# USB2Serial.net
KiCad netlist of a schematic drawn in Altium Designer
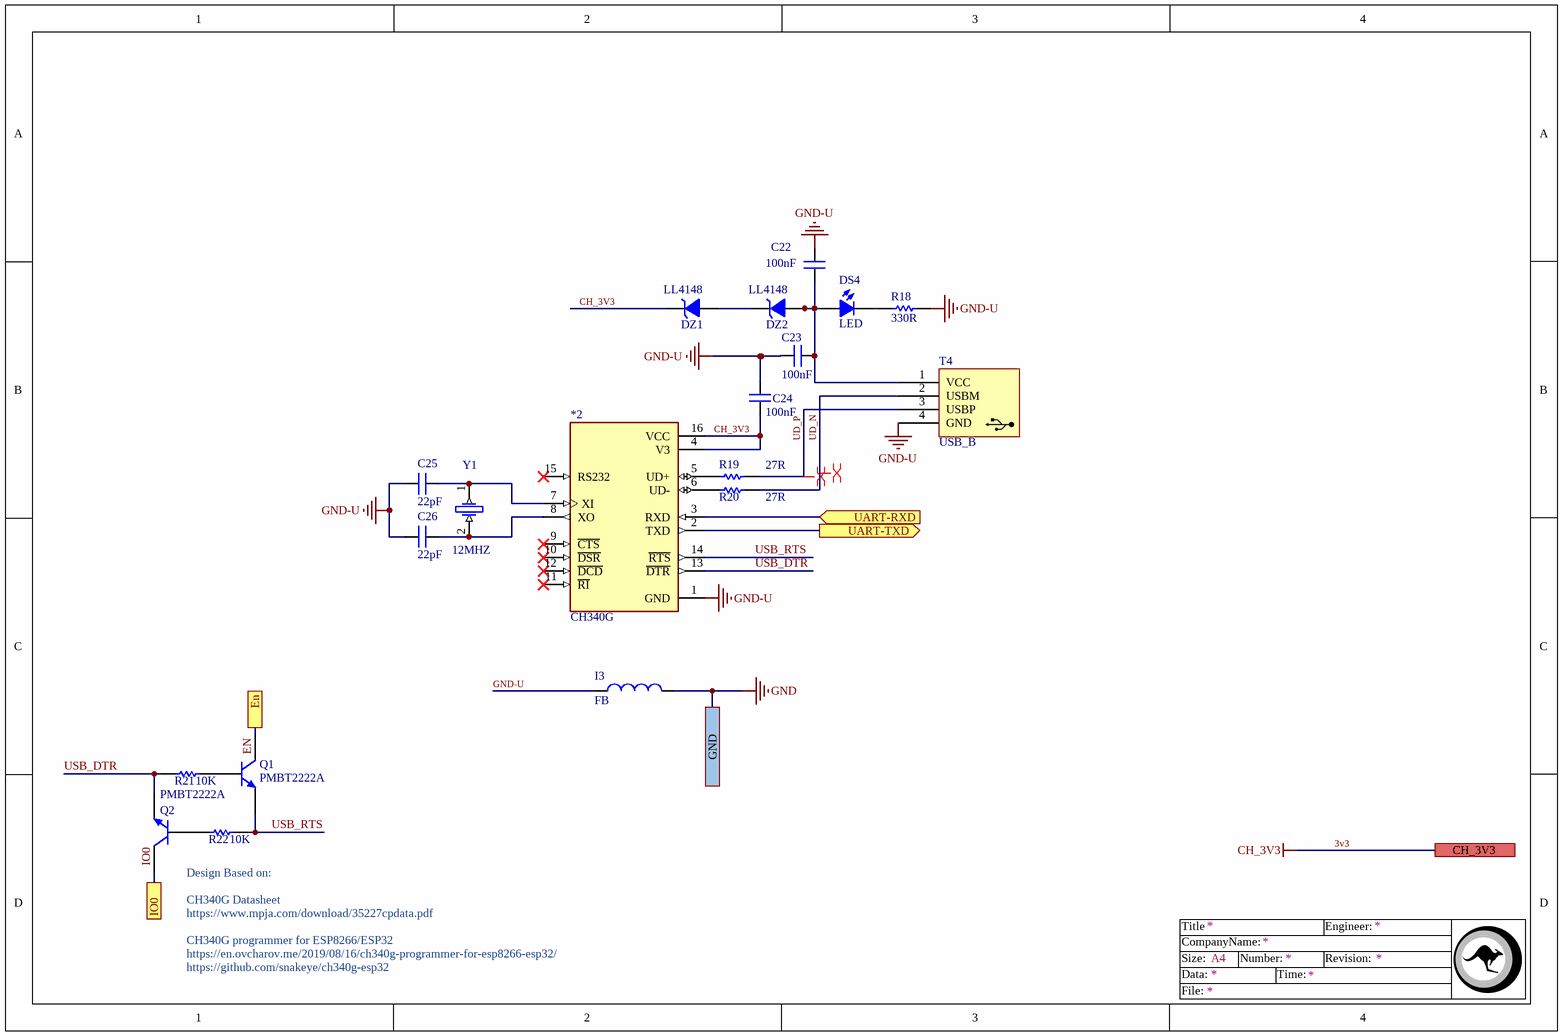
[diagram p0: USB2Serial.SchDoc]

(export (version "E")
  (design (tool "Eeschema 10.0.6"))
  (components
    (comp (ref "*2")
      (value "CH340G")
      (footprint "SOIC127P600X180-16N")
      (libsource (lib "PMLIB2020-V3") (part "CH340G"))
    )
    (comp (ref "C22")
      (value "100nF")
      (footprint "Cap0805")
      (description "Surface mount Capacitor")
      (libsource (lib "PMLIB2020-V3") (part "Cap"))
    )
    (comp (ref "C23")
      (value "100nF")
      (footprint "Cap0805")
      (description "Surface mount Capacitor")
      (libsource (lib "PMLIB2020-V3") (part "Cap"))
    )
    (comp (ref "C24")
      (value "100nF")
      (footprint "Cap0805")
      (description "Surface mount Capacitor")
      (libsource (lib "PMLIB2020-V3") (part "Cap"))
    )
    (comp (ref "C25")
      (value "22pF")
      (footprint "Cap0805")
      (description "Surface mount Capacitor")
      (libsource (lib "PMLIB2020-V3") (part "Cap"))
    )
    (comp (ref "C26")
      (value "22pF")
      (footprint "Cap0805")
      (description "Surface mount Capacitor")
      (libsource (lib "PMLIB2020-V3") (part "Cap"))
    )
    (comp (ref "DS4") (value "LED") (footprint "LED_0805Green") (libsource (lib "PMLIB2020-V3") (part "LED")))
    (comp (ref "DZ1")
      (value "LL4148")
      (footprint "LL4148")
      (description "Diode Zener")
      (libsource (lib "PMLIB2020-V3") (part "Diode Zener"))
    )
    (comp (ref "DZ2")
      (value "LL4148")
      (footprint "LL4148")
      (description "Diode Zener")
      (libsource (lib "PMLIB2020-V3") (part "Diode Zener"))
    )
    (comp (ref "I3")
      (value "FB")
      (footprint "1206")
      (description "Indicator")
      (libsource (lib "PMLIB2020-V3") (part "Inductor"))
    )
    (comp (ref "Q1")
      (value "PMBT2222A")
      (footprint "SOT23_BEC_N")
      (description "NPN Bipolar Transistor")
      (fields (field (name "PUBLISHER") "Altium Limited"))
      (libsource (lib "PMLIB2020-V3") (part "NPN"))
    )
    (comp (ref "Q2")
      (value "PMBT2222A")
      (footprint "SOT23_BEC_N")
      (description "NPN Bipolar Transistor")
      (fields (field (name "PUBLISHER") "Altium Limited"))
      (libsource (lib "PMLIB2020-V3") (part "NPN"))
    )
    (comp (ref "R18")
      (value "330R")
      (footprint "R0805")
      (description "Resistor")
      (libsource (lib "PMLIB2020-V3") (part "Resistor"))
    )
    (comp (ref "R19")
      (value "27R")
      (footprint "R0805")
      (description "Resistor")
      (libsource (lib "PMLIB2020-V3") (part "Resistor"))
    )
    (comp (ref "R20")
      (value "27R")
      (footprint "R0805")
      (description "Resistor")
      (libsource (lib "PMLIB2020-V3") (part "Resistor"))
    )
    (comp (ref "R21")
      (value "10K")
      (footprint "R0805")
      (description "Resistor")
      (libsource (lib "PMLIB2020-V3") (part "Resistor"))
    )
    (comp (ref "R22")
      (value "10K")
      (footprint "R0805")
      (description "Resistor")
      (libsource (lib "PMLIB2020-V3") (part "Resistor"))
    )
    (comp (ref "T4")
      (value "USB_B")
      (footprint "USB_Dip_R")
      (description "USB B Connector")
      (libsource (lib "PMLIB2020-V3") (part "USB_B"))
    )
    (comp (ref "Y1")
      (value "12MHZ")
      (footprint "Crystal SMD")
      (description "Crystal")
      (libsource (lib "PMLIB2020-V3") (part "Crystal"))
    )
  )
  (nets
    (net (code "2") (name "/En") (class "Default")
      (node (ref "Q1") (pin "3") (pinfunction "C_3") (pintype "passive"))
    )
    (net (code "3") (name "/IO0") (class "Default")
      (node (ref "Q2") (pin "3") (pinfunction "C_3") (pintype "passive"))
    )
    (net (code "4") (name "/UART-RXD") (class "Default")
      (node (ref "*2") (pin "3") (pinfunction "RXD_3") (pintype "input"))
    )
    (net (code "5") (name "/UART-TXD") (class "Default")
      (node (ref "*2") (pin "2") (pinfunction "TXD_2") (pintype "output"))
    )
    (net (code "6") (name "/UD_N") (class "Default")
      (node (ref "R20") (pin "1") (pinfunction "1_1") (pintype "passive"))
      (node (ref "T4") (pin "2") (pinfunction "USBM_2") (pintype "passive"))
    )
    (net (code "7") (name "/UD_P") (class "Default")
      (node (ref "R19") (pin "1") (pinfunction "1_1") (pintype "passive"))
      (node (ref "T4") (pin "3") (pinfunction "USBP_3") (pintype "passive"))
    )
    (net (code "8") (name "/USB_DTR") (class "Default")
      (node (ref "*2") (pin "13") (pinfunction "~{DTR}_13") (pintype "output"))
      (node (ref "Q2") (pin "2") (pinfunction "E_2") (pintype "passive"))
      (node (ref "R21") (pin "2") (pinfunction "2_2") (pintype "passive"))
    )
    (net (code "9") (name "/USB_RTS") (class "Default")
      (node (ref "*2") (pin "14") (pinfunction "~{RTS}_14") (pintype "output"))
      (node (ref "Q1") (pin "2") (pinfunction "E_2") (pintype "passive"))
      (node (ref "R22") (pin "1") (pinfunction "1_1") (pintype "passive"))
    )
    (net (code "10") (name "CH_3V3") (class "Default")
      (node (ref "*2") (pin "16") (pinfunction "VCC_16") (pintype "power_in"))
      (node (ref "*2") (pin "4") (pinfunction "V3_4") (pintype "power_in"))
      (node (ref "C24") (pin "2") (pinfunction "2_2") (pintype "passive"))
      (node (ref "DZ1") (pin "K") (pinfunction "K_K") (pintype "passive"))
    )
    (net (code "11") (name "GND") (class "Default")
      (node (ref "I3") (pin "2") (pinfunction "2_2") (pintype "passive"))
    )
    (net (code "12") (name "GND-U") (class "Default")
      (node (ref "*2") (pin "1") (pinfunction "GND_1") (pintype "power_in"))
      (node (ref "C22") (pin "2") (pinfunction "2_2") (pintype "passive"))
      (node (ref "C23") (pin "2") (pinfunction "2_2") (pintype "passive"))
      (node (ref "C24") (pin "1") (pinfunction "1_1") (pintype "passive"))
      (node (ref "C25") (pin "2") (pinfunction "2_2") (pintype "passive"))
      (node (ref "C26") (pin "2") (pinfunction "2_2") (pintype "passive"))
      (node (ref "I3") (pin "1") (pinfunction "1_1") (pintype "passive"))
      (node (ref "R18") (pin "1") (pinfunction "1_1") (pintype "passive"))
      (node (ref "T4") (pin "4") (pinfunction "GND_4") (pintype "passive"))
    )
    (net (code "13") (name "Net-(*2-UD+)") (class "Default")
      (node (ref "*2") (pin "5") (pinfunction "UD+_5") (pintype "bidirectional"))
      (node (ref "R19") (pin "2") (pinfunction "2_2") (pintype "passive"))
    )
    (net (code "14") (name "Net-(*2-UD-)") (class "Default")
      (node (ref "*2") (pin "6") (pinfunction "UD-_6") (pintype "bidirectional"))
      (node (ref "R20") (pin "2") (pinfunction "2_2") (pintype "passive"))
    )
    (net (code "15") (name "Net-(*2-XI)") (class "Default")
      (node (ref "*2") (pin "7") (pinfunction "XI_7") (pintype "input"))
      (node (ref "C25") (pin "1") (pinfunction "1_1") (pintype "passive"))
      (node (ref "Y1") (pin "1") (pinfunction "1_1") (pintype "output"))
    )
    (net (code "16") (name "Net-(*2-XO)") (class "Default")
      (node (ref "*2") (pin "8") (pinfunction "XO_8") (pintype "output"))
      (node (ref "C26") (pin "1") (pinfunction "1_1") (pintype "passive"))
      (node (ref "Y1") (pin "2") (pinfunction "2_2") (pintype "input"))
    )
    (net (code "17") (name "Net-(DS4-PadK)") (class "Default")
      (node (ref "DS4") (pin "K") (pinfunction "K_K") (pintype "passive"))
      (node (ref "R18") (pin "2") (pinfunction "2_2") (pintype "passive"))
    )
    (net (code "18") (name "Net-(DZ1-PadA)") (class "Default")
      (node (ref "DZ1") (pin "A") (pinfunction "A_A") (pintype "passive"))
      (node (ref "DZ2") (pin "K") (pinfunction "K_K") (pintype "passive"))
    )
    (net (code "19") (name "Net-(Q1-B)") (class "Default")
      (node (ref "Q1") (pin "1") (pinfunction "B_1") (pintype "passive"))
      (node (ref "R21") (pin "1") (pinfunction "1_1") (pintype "passive"))
    )
    (net (code "20") (name "Net-(Q2-B)") (class "Default")
      (node (ref "Q2") (pin "1") (pinfunction "B_1") (pintype "passive"))
      (node (ref "R22") (pin "2") (pinfunction "2_2") (pintype "passive"))
    )
    (net (code "21") (name "Net-(T4-VCC)") (class "Default")
      (node (ref "C22") (pin "1") (pinfunction "1_1") (pintype "passive"))
      (node (ref "C23") (pin "1") (pinfunction "1_1") (pintype "passive"))
      (node (ref "DS4") (pin "A") (pinfunction "A_A") (pintype "passive"))
      (node (ref "DZ2") (pin "A") (pinfunction "A_A") (pintype "passive"))
      (node (ref "T4") (pin "1") (pinfunction "VCC_1") (pintype "passive"))
    )
    (net (code "22") (name "unconnected-(*2-RS232-Pad15)") (class "Default")
      (node (ref "*2") (pin "15") (pinfunction "RS232_15") (pintype "input+no_connect"))
    )
    (net (code "23") (name "unconnected-(*2-~{CTS}-Pad9)") (class "Default")
      (node (ref "*2") (pin "9") (pinfunction "~{CTS}_9") (pintype "input+no_connect"))
    )
    (net (code "24") (name "unconnected-(*2-~{DCD}-Pad12)") (class "Default")
      (node (ref "*2") (pin "12") (pinfunction "~{DCD}_12") (pintype "input+no_connect"))
    )
    (net (code "25") (name "unconnected-(*2-~{DSR}-Pad10)") (class "Default")
      (node (ref "*2") (pin "10") (pinfunction "~{DSR}_10") (pintype "input+no_connect"))
    )
    (net (code "26") (name "unconnected-(*2-~{RI}-Pad11)") (class "Default")
      (node (ref "*2") (pin "11") (pinfunction "~{RI}_11") (pintype "input+no_connect"))
    )
  )
)
